# 03_-_MPU6050_SCH.net
KiCad netlist of a schematic drawn in Altium Designer
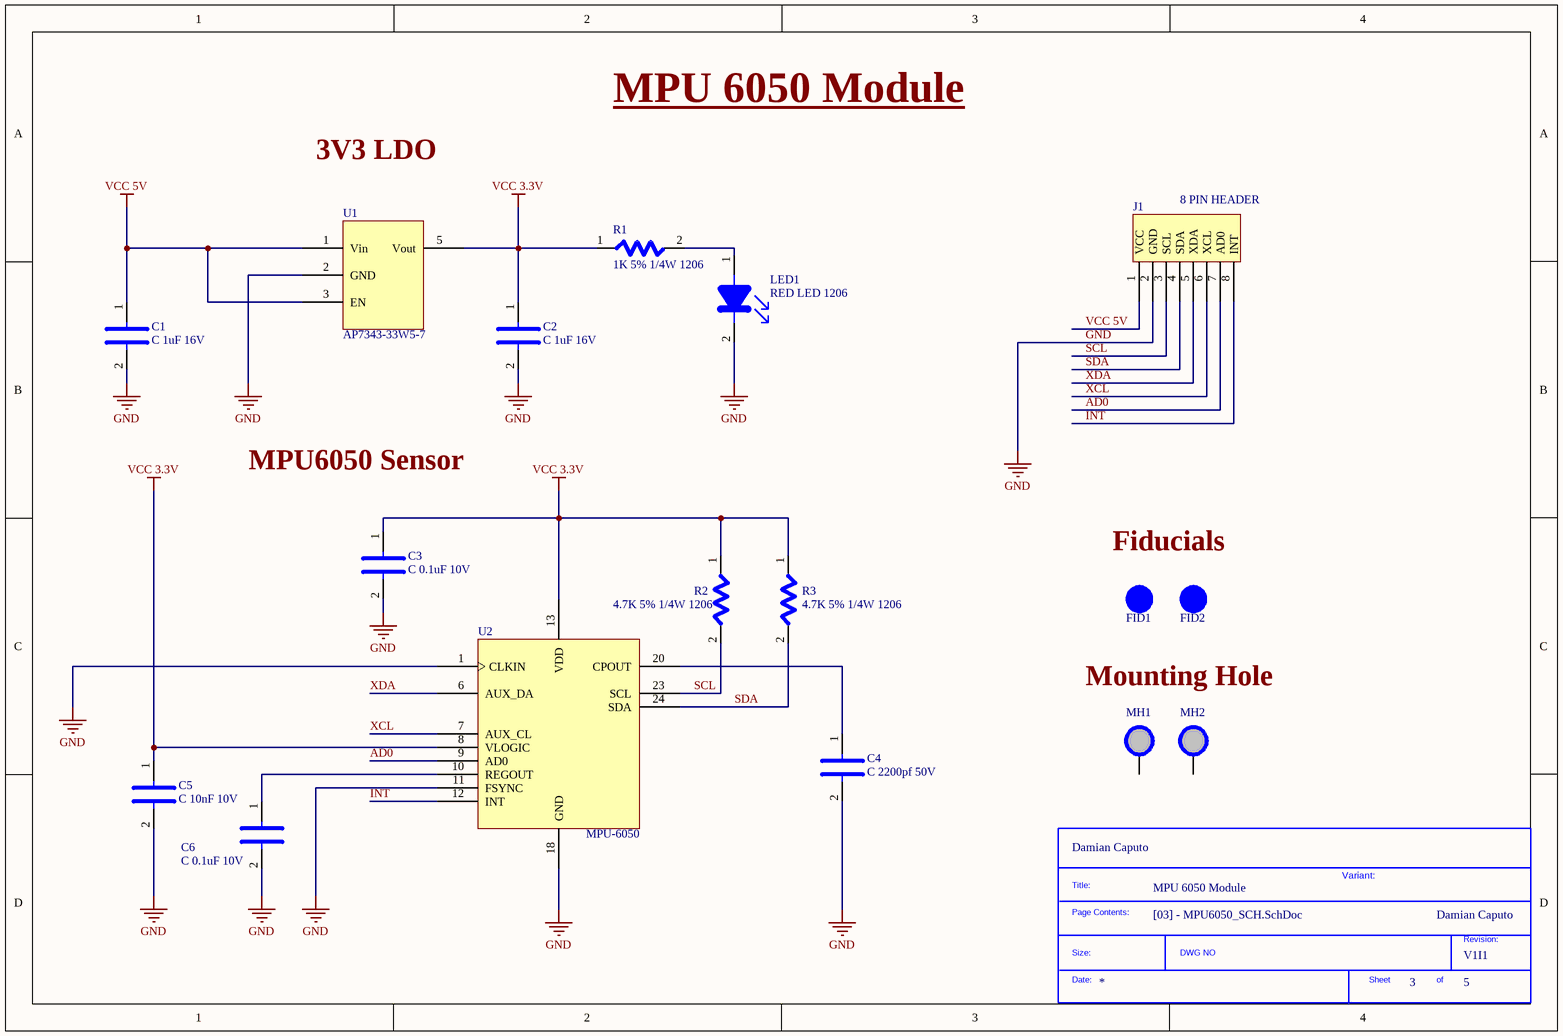
[diagram p0: [03] - MPU6050_SCH.SchDoc]

(export (version "E")
  (design (tool "Eeschema 10.0.6"))
  (components
    (comp (ref "C1")
      (value "C 1uF 16V")
      (footprint "CAP CER 1UF 10V X7R 1206")
      (description "1 µF ±10% 10V Capacitores cerámicos X7R 1206 (3216 métrico)")
      (fields (field (name "MANUFACTURER") "KEMET"))
      (libsource (lib "MPU6050_SCHLIB") (part "CAP CER 1UF 10V X7R 1206"))
    )
    (comp (ref "C2")
      (value "C 1uF 16V")
      (footprint "CAP CER 1UF 10V X7R 1206")
      (description "1 µF ±10% 10V Capacitores cerámicos X7R 1206 (3216 métrico)")
      (fields (field (name "MANUFACTURER") "KEMET"))
      (libsource (lib "MPU6050_SCHLIB") (part "CAP CER 1UF 10V X7R 1206"))
    )
    (comp (ref "C3")
      (value "C 0.1uF 10V")
      (footprint "CAP CER 0.1UF 10V X7R 1206")
      (description "0.1 µF ±10% 10V Capacitores cerámicos X7R 1206 (3216 métrico)")
      (fields (field (name "MANUFACTURER") "KEMET"))
      (libsource (lib "MPU6050_SCHLIB") (part "CAP CER 0.1UF 10V X7R 1206"))
    )
    (comp (ref "C4")
      (value "C 2200pf 50V")
      (footprint "CAP CER 2200PF 50V NP0 1206")
      (description "CAP CER 2200PF 50V NP0 1206")
      (fields (field (name "MANUFACTURER") "KEMET"))
      (libsource (lib "MPU6050_SCHLIB") (part "CAP CER 2200PF 50V NP0 1206"))
    )
    (comp (ref "C5")
      (value "C 10nF 10V")
      (footprint "CAP CER 1206 10NF 10V ULTRA STAB")
      (description "10000 pF ±1% 10V Capacitores cerámicos X8R 1206 (3216 métrico)")
      (fields (field (name "MANUFACTURER") "KEMET"))
      (libsource (lib "MPU6050_SCHLIB") (part "CAP CER 1206 10NF 10V ULTRA STAB"))
    )
    (comp (ref "C6")
      (value "C 0.1uF 10V")
      (footprint "CAP CER 0.1UF 10V X7R 1206")
      (description "0.1 µF ±10% 10V Capacitores cerámicos X7R 1206 (3216 métrico)")
      (fields (field (name "MANUFACTURER") "KEMET"))
      (libsource (lib "MPU6050_SCHLIB") (part "CAP CER 0.1UF 10V X7R 1206"))
    )
    (comp (ref "FID1")
      (value "FID_1mm")
      (footprint "FID_40_120")
      (description "Fiducial 40mil Diameter, 120mil Mask")
      (libsource (lib "MPU6050_SCHLIB") (part "FID_1mm"))
    )
    (comp (ref "FID2")
      (value "FID_1mm")
      (footprint "FID_40_120")
      (description "Fiducial 40mil Diameter, 120mil Mask")
      (libsource (lib "MPU6050_SCHLIB") (part "FID_1mm"))
    )
    (comp (ref "J1")
      (value "8 PIN HEADER")
      (footprint "CONN HEADER VERT 8POS 3.96MM")
      (description "Cabezal de conector Orificio pasante 8 posiciones 0.156\" (3.96mm)")
      (fields (field (name "MANUFACTURER") "TE Connectivity AMP Connectors"))
      (libsource (lib "MPU6050_SCHLIB") (part "CONN HEADER VERT 8POS 3.96MM"))
    )
    (comp (ref "LED1")
      (value "RED LED 1206")
      (footprint "RED LED 1206")
      (description "Rojo 630nm Indicación led: discreta 1.5V 1206 (3216 métrico)")
      (fields (field (name "MANUFACTURER") "Venkel"))
      (libsource (lib "MPU6050_SCHLIB") (part "LED 1206 FLAT LENS RED"))
    )
    (comp (ref "MH1")
      (value "MH_3.2mmD")
      (footprint "MH 7.4mmD 3.2mmDirll No plated")
      (description "MH 7..4mmD 3.2mmDrill Non plated")
      (libsource (lib "MPU6050_SCHLIB") (part "MH_3.2mmD"))
    )
    (comp (ref "MH2")
      (value "MH_3.2mmD")
      (footprint "MH 7.4mmD 3.2mmDirll No plated")
      (description "MH 7..4mmD 3.2mmDrill Non plated")
      (libsource (lib "MPU6050_SCHLIB") (part "MH_3.2mmD"))
    )
    (comp (ref "R1")
      (value "1K 5% 1/4W 1206")
      (footprint "RES SMD 1K OHM 5% 1/4W 1206")
      (description "1 kOhms ±5% 0.25W, 1/4W Resistencia en microprocesador 1206 (3216 métrico) - Película gruesa")
      (fields (field (name "MANUFACTURER") "Yageo"))
      (libsource (lib "MPU6050_SCHLIB") (part "RES SMD 1K OHM 5% 1/4W 1206"))
    )
    (comp (ref "R2")
      (value "4.7K 5% 1/4W 1206")
      (footprint "RES SMD 4.7K OHM 5% 1/4W 1206")
      (fields (field (name "MANUFACTURER") "Yageo"))
      (libsource (lib "MPU6050_SCHLIB") (part "RES 4.7K OHM 5% 1/4W 1206"))
    )
    (comp (ref "R3")
      (value "4.7K 5% 1/4W 1206")
      (footprint "RES SMD 4.7K OHM 5% 1/4W 1206")
      (fields (field (name "MANUFACTURER") "Yageo"))
      (libsource (lib "MPU6050_SCHLIB") (part "RES 4.7K OHM 5% 1/4W 1206"))
    )
    (comp (ref "U1")
      (value "AP7343-33W5-7")
      (footprint "AP7343-33W5-7")
      (description "Low dropout regulator with high output voltage. 3.3V 300mA")
      (fields (field (name "MANUFACTURER") "DIODES Incorporated"))
      (libsource (lib "MPU6050_SCHLIB") (part "AP7343-33W5-7"))
    )
    (comp (ref "U2")
      (value "MPU-6050")
      (footprint "MPU6050")
      (description "Acelerometer, gyro, 6 axis")
      (fields (field (name "MANUFACTURER") "TDK InvenSense"))
      (libsource (lib "MPU6050_SCHLIB") (part "MPU-6050"))
    )
  )
  (nets
    (net (code "1") (name "/AD0") (class "Default")
      (node (ref "J1") (pin "7") (pinfunction "AD0_7") (pintype "passive"))
      (node (ref "U2") (pin "9") (pinfunction "AD0_9") (pintype "passive"))
    )
    (net (code "2") (name "/INT") (class "Default")
      (node (ref "J1") (pin "8") (pinfunction "INT_8") (pintype "passive"))
      (node (ref "U2") (pin "12") (pinfunction "INT_12") (pintype "passive"))
    )
    (net (code "3") (name "/SCL") (class "Default")
      (node (ref "J1") (pin "3") (pinfunction "SCL_3") (pintype "passive"))
      (node (ref "R2") (pin "2") (pinfunction "2_2") (pintype "passive"))
      (node (ref "U2") (pin "23") (pinfunction "SCL_23") (pintype "passive"))
    )
    (net (code "4") (name "/SDA") (class "Default")
      (node (ref "J1") (pin "4") (pinfunction "SDA_4") (pintype "passive"))
      (node (ref "R3") (pin "2") (pinfunction "2_2") (pintype "passive"))
      (node (ref "U2") (pin "24") (pinfunction "SDA_24") (pintype "passive"))
    )
    (net (code "5") (name "/XCL") (class "Default")
      (node (ref "J1") (pin "6") (pinfunction "XCL_6") (pintype "passive"))
      (node (ref "U2") (pin "7") (pinfunction "AUX_CL_7") (pintype "passive"))
    )
    (net (code "6") (name "/XDA") (class "Default")
      (node (ref "J1") (pin "5") (pinfunction "XDA_5") (pintype "passive"))
      (node (ref "U2") (pin "6") (pinfunction "AUX_DA_6") (pintype "passive"))
    )
    (net (code "7") (name "GND") (class "Default")
      (node (ref "C1") (pin "2") (pinfunction "2_2") (pintype "passive"))
      (node (ref "C2") (pin "2") (pinfunction "2_2") (pintype "passive"))
      (node (ref "C3") (pin "2") (pinfunction "2_2") (pintype "passive"))
      (node (ref "C4") (pin "2") (pinfunction "2_2") (pintype "passive"))
      (node (ref "C5") (pin "2") (pinfunction "2_2") (pintype "passive"))
      (node (ref "C6") (pin "2") (pinfunction "2_2") (pintype "passive"))
      (node (ref "J1") (pin "2") (pinfunction "GND_2") (pintype "passive"))
      (node (ref "LED1") (pin "2") (pinfunction "2_2") (pintype "passive"))
      (node (ref "U1") (pin "2") (pinfunction "GND_2") (pintype "passive"))
      (node (ref "U2") (pin "1") (pinfunction "CLKIN_1") (pintype "passive"))
      (node (ref "U2") (pin "11") (pinfunction "FSYNC_11") (pintype "passive"))
      (node (ref "U2") (pin "18") (pinfunction "GND_18") (pintype "passive"))
    )
    (net (code "8") (name "Net-(LED1-Pad1)") (class "Default")
      (node (ref "LED1") (pin "1") (pinfunction "1_1") (pintype "passive"))
      (node (ref "R1") (pin "2") (pinfunction "2_2") (pintype "passive"))
    )
    (net (code "9") (name "Net-(U2-CPOUT)") (class "Default")
      (node (ref "C4") (pin "1") (pinfunction "1_1") (pintype "passive"))
      (node (ref "U2") (pin "20") (pinfunction "CPOUT_20") (pintype "passive"))
    )
    (net (code "10") (name "Net-(U2-REGOUT)") (class "Default")
      (node (ref "C6") (pin "1") (pinfunction "1_1") (pintype "passive"))
      (node (ref "U2") (pin "10") (pinfunction "REGOUT_10") (pintype "passive"))
    )
    (net (code "11") (name "VCC 3.3V") (class "Default")
      (node (ref "C2") (pin "1") (pinfunction "1_1") (pintype "passive"))
      (node (ref "C3") (pin "1") (pinfunction "1_1") (pintype "passive"))
      (node (ref "C5") (pin "1") (pinfunction "1_1") (pintype "passive"))
      (node (ref "R1") (pin "1") (pinfunction "1_1") (pintype "passive"))
      (node (ref "R2") (pin "1") (pinfunction "1_1") (pintype "passive"))
      (node (ref "R3") (pin "1") (pinfunction "1_1") (pintype "passive"))
      (node (ref "U1") (pin "5") (pinfunction "Vout_5") (pintype "passive"))
      (node (ref "U2") (pin "13") (pinfunction "VDD_13") (pintype "passive"))
      (node (ref "U2") (pin "8") (pinfunction "VLOGIC_8") (pintype "passive"))
    )
    (net (code "12") (name "VCC 5V") (class "Default")
      (node (ref "C1") (pin "1") (pinfunction "1_1") (pintype "passive"))
      (node (ref "J1") (pin "1") (pinfunction "VCC_1") (pintype "passive"))
      (node (ref "U1") (pin "1") (pinfunction "Vin_1") (pintype "passive"))
      (node (ref "U1") (pin "3") (pinfunction "EN_3") (pintype "passive"))
    )
    (net (code "13") (name "unconnected-(MH1-Pad1)") (class "Default")
      (node (ref "MH1") (pin "1") (pinfunction "1_1") (pintype "passive"))
    )
    (net (code "14") (name "unconnected-(MH2-Pad1)") (class "Default")
      (node (ref "MH2") (pin "1") (pinfunction "1_1") (pintype "passive"))
    )
  )
)
